# Qwiic_ADC.net
KiCad netlist of a schematic drawn in EAGLE
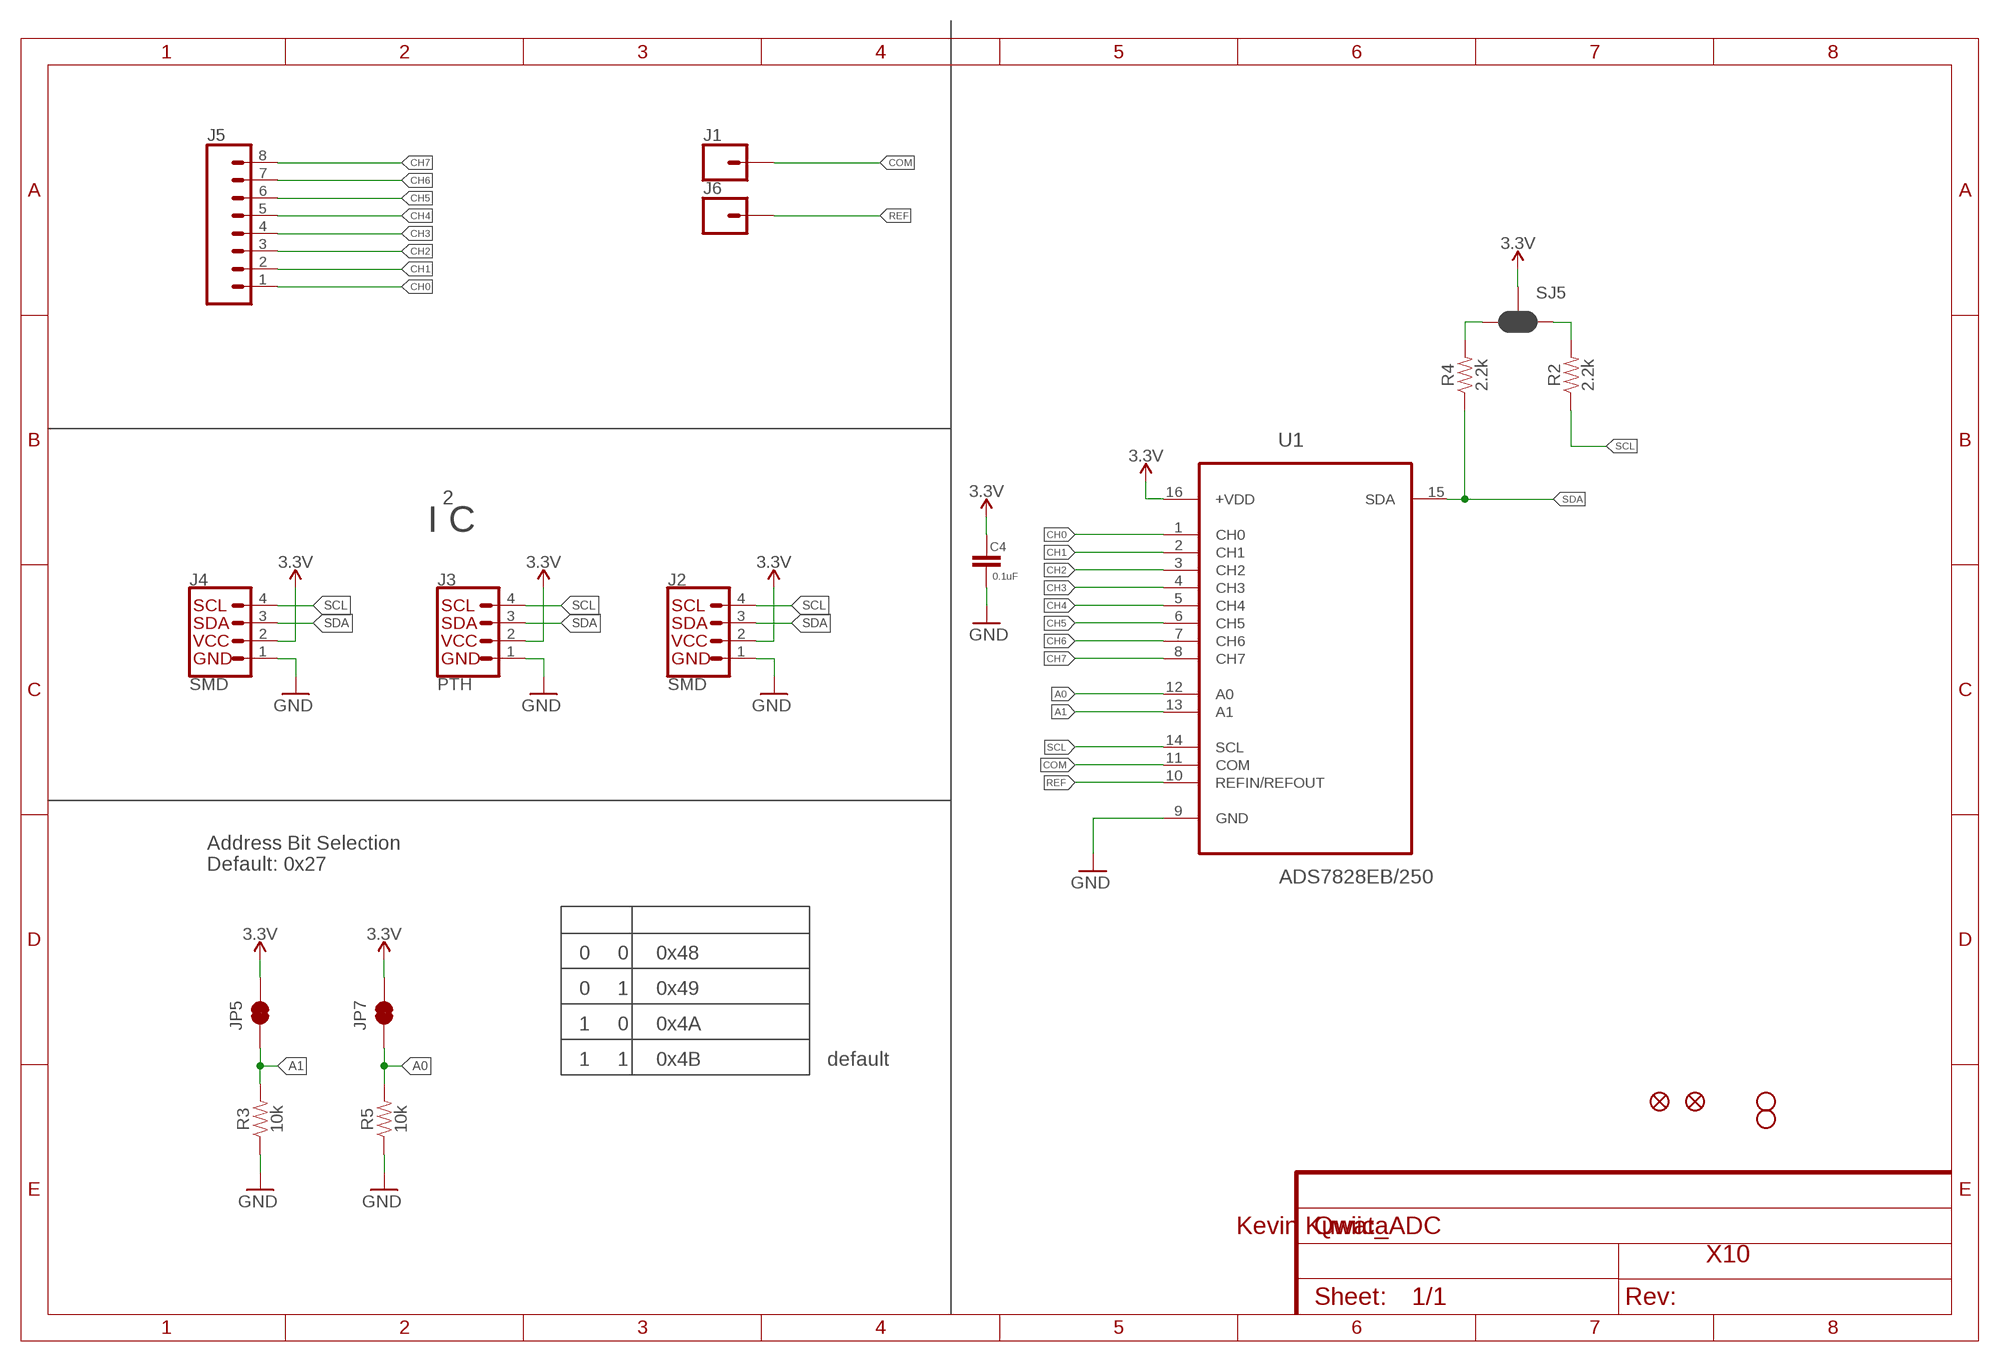
[diagram p0: schematic, sheet 1]

(export (version "E")
  (design (tool "Eeschema 10.0.6"))
  (components
    (comp (ref "C4")
      (value "0.1uF")
      (footprint "eagle-import:0603")
      (libsource (lib "eagle-import") (part "0.1UF-0603-25V-(+80/-20%)"))
    )
    (comp (ref "J1")
      (value "CONN_01PTH_NO_SILK_YES_STOP")
      (footprint "eagle-import:1X01_NO_SILK")
      (libsource (lib "eagle-import") (part "CONN_01PTH_NO_SILK_YES_STOP"))
    )
    (comp (ref "J2")
      (value "SMD")
      (footprint "eagle-import:1X04_1MM_RA")
      (libsource (lib "eagle-import") (part "I2C_STANDARDJS-1MM"))
    )
    (comp (ref "J3")
      (value "PTH")
      (footprint "eagle-import:1X04_NO_SILK")
      (libsource (lib "eagle-import") (part "I2C_STANDARD_NO_SILK"))
    )
    (comp (ref "J4")
      (value "SMD")
      (footprint "eagle-import:1X04_1MM_RA")
      (libsource (lib "eagle-import") (part "I2C_STANDARDJS-1MM"))
    )
    (comp (ref "J5")
      (value "CONN_08NO_SILK_FEMALE_PTH")
      (footprint "eagle-import:1X08_NO_SILK")
      (libsource (lib "eagle-import") (part "CONN_08NO_SILK_FEMALE_PTH"))
    )
    (comp (ref "J6")
      (value "CONN_01PTH_NO_SILK_YES_STOP")
      (footprint "eagle-import:1X01_NO_SILK")
      (libsource (lib "eagle-import") (part "CONN_01PTH_NO_SILK_YES_STOP"))
    )
    (comp (ref "JP2")
      (value "FIDUCIALUFIDUCIAL")
      (footprint "eagle-import:MICRO-FIDUCIAL")
      (libsource (lib "eagle-import") (part "FIDUCIALUFIDUCIAL"))
    )
    (comp (ref "JP3")
      (value "STAND-OFF")
      (footprint "eagle-import:STAND-OFF")
      (libsource (lib "eagle-import") (part "STAND-OFF"))
    )
    (comp (ref "JP4")
      (value "STAND-OFF")
      (footprint "eagle-import:STAND-OFF")
      (libsource (lib "eagle-import") (part "STAND-OFF"))
    )
    (comp (ref "JP5")
      (value "JUMPER-SMT_2_NC_TRACE_NO-SILK")
      (footprint "eagle-import:SMT-JUMPER_2_NC_TRACE_NO-SILK")
      (libsource (lib "eagle-import") (part "JUMPER-SMT_2_NC_TRACE_NO-SILK"))
    )
    (comp (ref "JP6")
      (value "FIDUCIALUFIDUCIAL")
      (footprint "eagle-import:MICRO-FIDUCIAL")
      (libsource (lib "eagle-import") (part "FIDUCIALUFIDUCIAL"))
    )
    (comp (ref "JP7")
      (value "JUMPER-SMT_2_NC_TRACE_NO-SILK")
      (footprint "eagle-import:SMT-JUMPER_2_NC_TRACE_NO-SILK")
      (libsource (lib "eagle-import") (part "JUMPER-SMT_2_NC_TRACE_NO-SILK"))
    )
    (comp (ref "R2")
      (value "2.2k")
      (footprint "eagle-import:0603")
      (libsource (lib "eagle-import") (part "2.2KOHM-0603-1/10W-1%"))
    )
    (comp (ref "R3")
      (value "10k")
      (footprint "eagle-import:0603")
      (libsource (lib "eagle-import") (part "2.2KOHM-0603-1/10W-1%"))
    )
    (comp (ref "R4")
      (value "2.2k")
      (footprint "eagle-import:0603")
      (libsource (lib "eagle-import") (part "2.2KOHM-0603-1/10W-1%"))
    )
    (comp (ref "R5")
      (value "10k")
      (footprint "eagle-import:0603")
      (libsource (lib "eagle-import") (part "2.2KOHM-0603-1/10W-1%"))
    )
    (comp (ref "SJ5")
      (value "SMT-JUMPER-_3-2-NC-PASTE_TALL")
      (footprint "eagle-import:SMT-JUMPER_3-2-NC-PASTE_SILK_TALLER_A")
      (libsource (lib "eagle-import") (part "SMT-JUMPER-_3-2-NC-PASTE_TALL"))
    )
    (comp (ref "U1")
      (value "ADS7828EB/250")
      (footprint "eagle-import:SOP65P640X120-16N")
      (fields (field (name "MF") "Texas"))
      (libsource (lib "eagle-import") (part "ADS7828EB/250"))
    )
  )
  (nets
    (net (code "1") (name "3.3V") (class "Default")
      (node (ref "C4") (pin "1") (pinfunction "1_1") (pintype "passive"))
      (node (ref "J2") (pin "2") (pinfunction "VCC_2") (pintype "power_in"))
      (node (ref "J3") (pin "2") (pinfunction "VCC_2") (pintype "power_in"))
      (node (ref "J4") (pin "2") (pinfunction "VCC_2") (pintype "power_in"))
      (node (ref "JP5") (pin "2") (pinfunction "2_2") (pintype "passive"))
      (node (ref "JP7") (pin "2") (pinfunction "2_2") (pintype "passive"))
      (node (ref "SJ5") (pin "2") (pinfunction "2_2") (pintype "passive"))
      (node (ref "U1") (pin "16") (pinfunction "+VDD_16") (pintype "power_in"))
    )
    (net (code "2") (name "A0") (class "Default")
      (node (ref "JP7") (pin "1") (pinfunction "1_1") (pintype "passive"))
      (node (ref "R5") (pin "2") (pinfunction "2_2") (pintype "passive"))
      (node (ref "U1") (pin "12") (pinfunction "A0_12") (pintype "input"))
    )
    (net (code "3") (name "A1") (class "Default")
      (node (ref "JP5") (pin "1") (pinfunction "1_1") (pintype "passive"))
      (node (ref "R3") (pin "2") (pinfunction "2_2") (pintype "passive"))
      (node (ref "U1") (pin "13") (pinfunction "A1_13") (pintype "input"))
    )
    (net (code "4") (name "CH0") (class "Default")
      (node (ref "J5") (pin "1") (pinfunction "1_1") (pintype "passive"))
      (node (ref "U1") (pin "1") (pinfunction "CH0_1") (pintype "input"))
    )
    (net (code "5") (name "CH1") (class "Default")
      (node (ref "J5") (pin "2") (pinfunction "2_2") (pintype "passive"))
      (node (ref "U1") (pin "2") (pinfunction "CH1_2") (pintype "input"))
    )
    (net (code "6") (name "CH2") (class "Default")
      (node (ref "J5") (pin "3") (pinfunction "3_3") (pintype "passive"))
      (node (ref "U1") (pin "3") (pinfunction "CH2_3") (pintype "input"))
    )
    (net (code "7") (name "CH3") (class "Default")
      (node (ref "J5") (pin "4") (pinfunction "4_4") (pintype "passive"))
      (node (ref "U1") (pin "4") (pinfunction "CH3_4") (pintype "input"))
    )
    (net (code "8") (name "CH4") (class "Default")
      (node (ref "J5") (pin "5") (pinfunction "5_5") (pintype "passive"))
      (node (ref "U1") (pin "5") (pinfunction "CH4_5") (pintype "input"))
    )
    (net (code "9") (name "CH5") (class "Default")
      (node (ref "J5") (pin "6") (pinfunction "6_6") (pintype "passive"))
      (node (ref "U1") (pin "6") (pinfunction "CH5_6") (pintype "input"))
    )
    (net (code "10") (name "CH6") (class "Default")
      (node (ref "J5") (pin "7") (pinfunction "7_7") (pintype "passive"))
      (node (ref "U1") (pin "7") (pinfunction "CH6_7") (pintype "input"))
    )
    (net (code "11") (name "CH7") (class "Default")
      (node (ref "J5") (pin "8") (pinfunction "8_8") (pintype "passive"))
      (node (ref "U1") (pin "8") (pinfunction "CH7_8") (pintype "input"))
    )
    (net (code "12") (name "COM") (class "Default")
      (node (ref "J1") (pin "1") (pinfunction "1_1") (pintype "passive"))
      (node (ref "U1") (pin "11") (pinfunction "COM_11") (pintype "input"))
    )
    (net (code "13") (name "GND") (class "Default")
      (node (ref "C4") (pin "2") (pinfunction "2_2") (pintype "passive"))
      (node (ref "J2") (pin "1") (pinfunction "GND_1") (pintype "power_in"))
      (node (ref "J3") (pin "1") (pinfunction "GND_1") (pintype "power_in"))
      (node (ref "J4") (pin "1") (pinfunction "GND_1") (pintype "power_in"))
      (node (ref "R3") (pin "1") (pinfunction "1_1") (pintype "passive"))
      (node (ref "R5") (pin "1") (pinfunction "1_1") (pintype "passive"))
      (node (ref "U1") (pin "9") (pinfunction "GND_9") (pintype "passive"))
    )
    (net (code "14") (name "Net-(R2-Pad2)") (class "Default")
      (node (ref "R2") (pin "2") (pinfunction "2_2") (pintype "passive"))
      (node (ref "SJ5") (pin "1") (pinfunction "1_1") (pintype "passive"))
    )
    (net (code "15") (name "Net-(R4-Pad2)") (class "Default")
      (node (ref "R4") (pin "2") (pinfunction "2_2") (pintype "passive"))
      (node (ref "SJ5") (pin "3") (pinfunction "3_3") (pintype "passive"))
    )
    (net (code "16") (name "REF") (class "Default")
      (node (ref "J6") (pin "1") (pinfunction "1_1") (pintype "passive"))
      (node (ref "U1") (pin "10") (pinfunction "REFIN/REFOUT_10") (pintype "bidirectional"))
    )
    (net (code "17") (name "SCL") (class "Default")
      (node (ref "J2") (pin "4") (pinfunction "SCL_4") (pintype "passive"))
      (node (ref "J3") (pin "4") (pinfunction "SCL_4") (pintype "passive"))
      (node (ref "J4") (pin "4") (pinfunction "SCL_4") (pintype "passive"))
      (node (ref "R2") (pin "1") (pinfunction "1_1") (pintype "passive"))
      (node (ref "U1") (pin "14") (pinfunction "SCL_14") (pintype "input"))
    )
    (net (code "18") (name "SDA") (class "Default")
      (node (ref "J2") (pin "3") (pinfunction "SDA_3") (pintype "passive"))
      (node (ref "J3") (pin "3") (pinfunction "SDA_3") (pintype "passive"))
      (node (ref "J4") (pin "3") (pinfunction "SDA_3") (pintype "passive"))
      (node (ref "R4") (pin "1") (pinfunction "1_1") (pintype "passive"))
      (node (ref "U1") (pin "15") (pinfunction "SDA_15") (pintype "bidirectional"))
    )
  )
)
